# ELED04.net
KiCad netlist of a schematic drawn in EAGLE
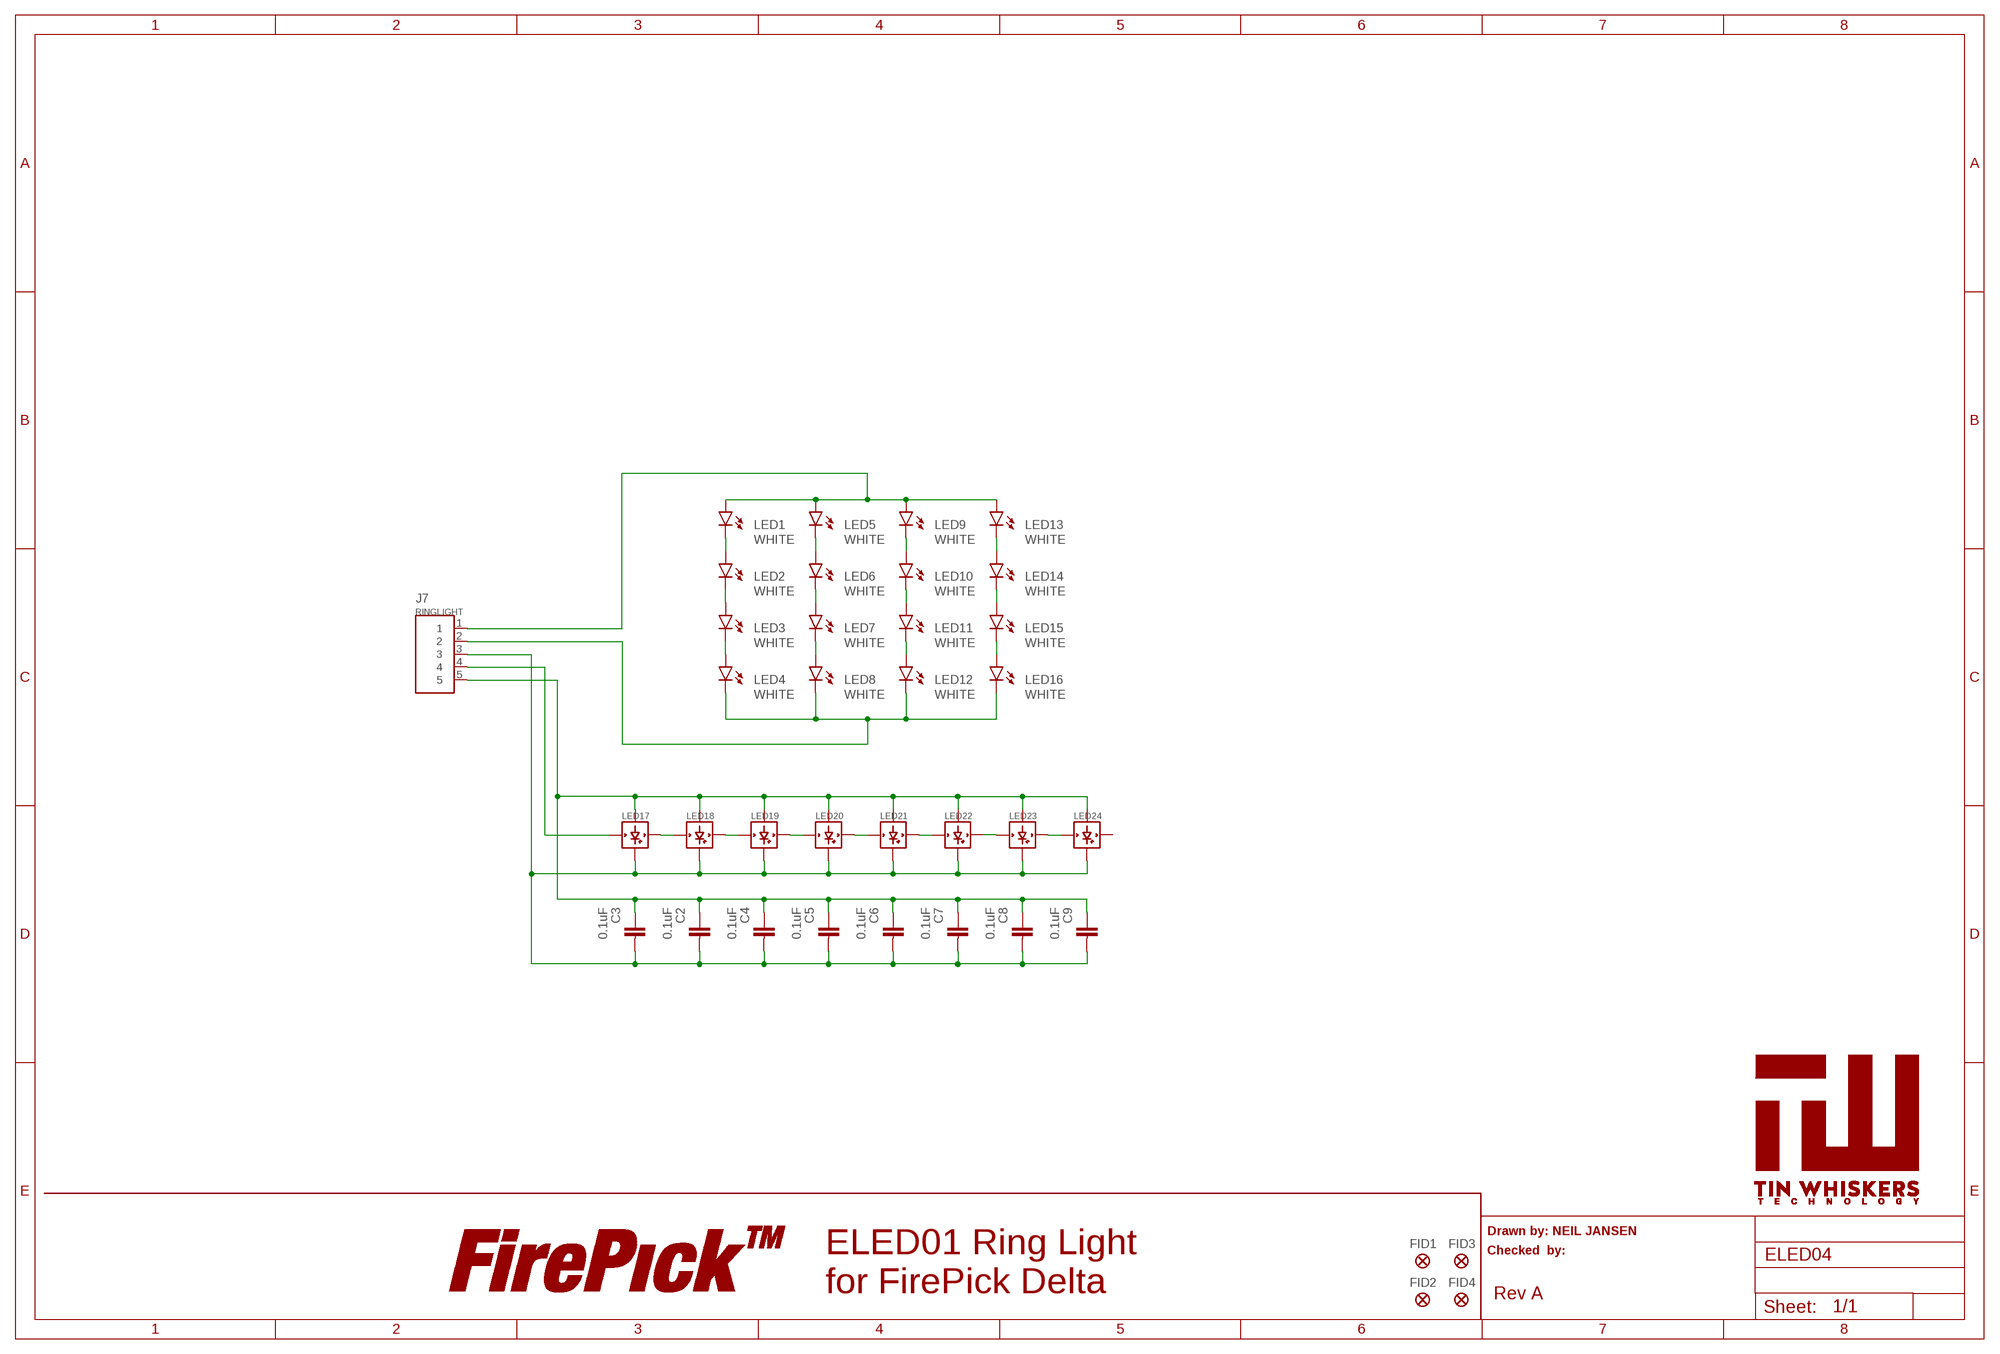
[diagram p0: schematic, sheet 1]

(export (version "E")
  (design (tool "Eeschema 10.0.6"))
  (components
    (comp (ref "C2")
      (value "0.1uF")
      (footprint "eagle-import:C0603")
      (fields (field (name "PARTNO") "GMK107BJ104KAHT"))
      (libsource (lib "eagle-import") (part "CPL-CAP-X5R-0603-0.1UF-35V"))
    )
    (comp (ref "C3")
      (value "0.1uF")
      (footprint "eagle-import:C0603")
      (fields (field (name "PARTNO") "GMK107BJ104KAHT"))
      (libsource (lib "eagle-import") (part "CPL-CAP-X5R-0603-0.1UF-35V"))
    )
    (comp (ref "C4")
      (value "0.1uF")
      (footprint "eagle-import:C0603")
      (fields (field (name "PARTNO") "GMK107BJ104KAHT"))
      (libsource (lib "eagle-import") (part "CPL-CAP-X5R-0603-0.1UF-35V"))
    )
    (comp (ref "C5")
      (value "0.1uF")
      (footprint "eagle-import:C0603")
      (fields (field (name "PARTNO") "GMK107BJ104KAHT"))
      (libsource (lib "eagle-import") (part "CPL-CAP-X5R-0603-0.1UF-35V"))
    )
    (comp (ref "C6")
      (value "0.1uF")
      (footprint "eagle-import:C0603")
      (fields (field (name "PARTNO") "GMK107BJ104KAHT"))
      (libsource (lib "eagle-import") (part "CPL-CAP-X5R-0603-0.1UF-35V"))
    )
    (comp (ref "C7")
      (value "0.1uF")
      (footprint "eagle-import:C0603")
      (fields (field (name "PARTNO") "GMK107BJ104KAHT"))
      (libsource (lib "eagle-import") (part "CPL-CAP-X5R-0603-0.1UF-35V"))
    )
    (comp (ref "C8")
      (value "0.1uF")
      (footprint "eagle-import:C0603")
      (fields (field (name "PARTNO") "GMK107BJ104KAHT"))
      (libsource (lib "eagle-import") (part "CPL-CAP-X5R-0603-0.1UF-35V"))
    )
    (comp (ref "C9")
      (value "0.1uF")
      (footprint "eagle-import:C0603")
      (fields (field (name "PARTNO") "GMK107BJ104KAHT"))
      (libsource (lib "eagle-import") (part "CPL-CAP-X5R-0603-0.1UF-35V"))
    )
    (comp (ref "FID1")
      (value "FIDUCIAL")
      (footprint "eagle-import:FIDUCIAL")
      (libsource (lib "eagle-import") (part "FIDUCIAL"))
    )
    (comp (ref "FID2")
      (value "FIDUCIAL")
      (footprint "eagle-import:FIDUCIAL")
      (libsource (lib "eagle-import") (part "FIDUCIAL"))
    )
    (comp (ref "FID3")
      (value "FIDUCIAL")
      (footprint "eagle-import:FIDUCIAL")
      (libsource (lib "eagle-import") (part "FIDUCIAL"))
    )
    (comp (ref "FID4")
      (value "FIDUCIAL")
      (footprint "eagle-import:FIDUCIAL")
      (libsource (lib "eagle-import") (part "FIDUCIAL"))
    )
    (comp (ref "J7")
      (value "RINGLIGHT")
      (footprint "eagle-import:CON-JST-PH-2.0MM-5P-SMT-VRT")
      (fields (field (name "PARTNO") "B5B-PH-SM4-TB(LF)(SN)"))
      (libsource (lib "eagle-import") (part "CPL-CON-JST-2.0MM-5P-SMT-VRT"))
    )
    (comp (ref "LED1")
      (value "WHITE")
      (footprint "eagle-import:DIODE-1210")
      (fields (field (name "PARTNO") "QBLP650-IW"))
      (libsource (lib "eagle-import") (part "LED1210"))
    )
    (comp (ref "LED2")
      (value "WHITE")
      (footprint "eagle-import:DIODE-1210")
      (fields (field (name "PARTNO") "QBLP650-IW"))
      (libsource (lib "eagle-import") (part "LED1210"))
    )
    (comp (ref "LED3")
      (value "WHITE")
      (footprint "eagle-import:DIODE-1210")
      (fields (field (name "PARTNO") "QBLP650-IW"))
      (libsource (lib "eagle-import") (part "LED1210"))
    )
    (comp (ref "LED4")
      (value "WHITE")
      (footprint "eagle-import:DIODE-1210")
      (fields (field (name "PARTNO") "QBLP650-IW"))
      (libsource (lib "eagle-import") (part "LED1210"))
    )
    (comp (ref "LED5")
      (value "WHITE")
      (footprint "eagle-import:DIODE-1210")
      (fields (field (name "PARTNO") "QBLP650-IW"))
      (libsource (lib "eagle-import") (part "LED1210"))
    )
    (comp (ref "LED6")
      (value "WHITE")
      (footprint "eagle-import:DIODE-1210")
      (fields (field (name "PARTNO") "QBLP650-IW"))
      (libsource (lib "eagle-import") (part "LED1210"))
    )
    (comp (ref "LED7")
      (value "WHITE")
      (footprint "eagle-import:DIODE-1210")
      (fields (field (name "PARTNO") "QBLP650-IW"))
      (libsource (lib "eagle-import") (part "LED1210"))
    )
    (comp (ref "LED8")
      (value "WHITE")
      (footprint "eagle-import:DIODE-1210")
      (fields (field (name "PARTNO") "QBLP650-IW"))
      (libsource (lib "eagle-import") (part "LED1210"))
    )
    (comp (ref "LED9")
      (value "WHITE")
      (footprint "eagle-import:DIODE-1210")
      (fields (field (name "PARTNO") "QBLP650-IW"))
      (libsource (lib "eagle-import") (part "LED1210"))
    )
    (comp (ref "LED10")
      (value "WHITE")
      (footprint "eagle-import:DIODE-1210")
      (fields (field (name "PARTNO") "QBLP650-IW"))
      (libsource (lib "eagle-import") (part "LED1210"))
    )
    (comp (ref "LED11")
      (value "WHITE")
      (footprint "eagle-import:DIODE-1210")
      (fields (field (name "PARTNO") "QBLP650-IW"))
      (libsource (lib "eagle-import") (part "LED1210"))
    )
    (comp (ref "LED12")
      (value "WHITE")
      (footprint "eagle-import:DIODE-1210")
      (fields (field (name "PARTNO") "QBLP650-IW"))
      (libsource (lib "eagle-import") (part "LED1210"))
    )
    (comp (ref "LED13")
      (value "WHITE")
      (footprint "eagle-import:DIODE-1210")
      (fields (field (name "PARTNO") "QBLP650-IW"))
      (libsource (lib "eagle-import") (part "LED1210"))
    )
    (comp (ref "LED14")
      (value "WHITE")
      (footprint "eagle-import:DIODE-1210")
      (fields (field (name "PARTNO") "QBLP650-IW"))
      (libsource (lib "eagle-import") (part "LED1210"))
    )
    (comp (ref "LED15")
      (value "WHITE")
      (footprint "eagle-import:DIODE-1210")
      (fields (field (name "PARTNO") "QBLP650-IW"))
      (libsource (lib "eagle-import") (part "LED1210"))
    )
    (comp (ref "LED16")
      (value "WHITE")
      (footprint "eagle-import:DIODE-1210")
      (fields (field (name "PARTNO") "QBLP650-IW"))
      (libsource (lib "eagle-import") (part "LED1210"))
    )
    (comp (ref "LED17")
      (value "WS2812B")
      (footprint "eagle-import:WS2812B")
      (fields (field (name "PARTNO") "1655"))
      (libsource (lib "eagle-import") (part "WS2812B"))
    )
    (comp (ref "LED18")
      (value "WS2812B")
      (footprint "eagle-import:WS2812B")
      (fields (field (name "PARTNO") "1655"))
      (libsource (lib "eagle-import") (part "WS2812B"))
    )
    (comp (ref "LED19")
      (value "WS2812B")
      (footprint "eagle-import:WS2812B")
      (fields (field (name "PARTNO") "1655"))
      (libsource (lib "eagle-import") (part "WS2812B"))
    )
    (comp (ref "LED20")
      (value "WS2812B")
      (footprint "eagle-import:WS2812B")
      (fields (field (name "PARTNO") "1655"))
      (libsource (lib "eagle-import") (part "WS2812B"))
    )
    (comp (ref "LED21")
      (value "WS2812B")
      (footprint "eagle-import:WS2812B")
      (fields (field (name "PARTNO") "1655"))
      (libsource (lib "eagle-import") (part "WS2812B"))
    )
    (comp (ref "LED22")
      (value "WS2812B")
      (footprint "eagle-import:WS2812B")
      (fields (field (name "PARTNO") "1655"))
      (libsource (lib "eagle-import") (part "WS2812B"))
    )
    (comp (ref "LED23")
      (value "WS2812B")
      (footprint "eagle-import:WS2812B")
      (fields (field (name "PARTNO") "1655"))
      (libsource (lib "eagle-import") (part "WS2812B"))
    )
    (comp (ref "LED24")
      (value "WS2812B")
      (footprint "eagle-import:WS2812B")
      (fields (field (name "PARTNO") "1655"))
      (libsource (lib "eagle-import") (part "WS2812B"))
    )
    (comp (ref "LOGO4")
      (value "LOGO-FIREPICKMEDIUM")
      (footprint "eagle-import:LOGO-FIREPICK-MEDIUM")
      (libsource (lib "eagle-import") (part "LOGO-FIREPICKMEDIUM"))
    )
    (comp (ref "U$3")
      (value "TIN-WHISKERSSMALL")
      (footprint "eagle-import:TIN-WHISKERS-SMALL")
      (libsource (lib "eagle-import") (part "TIN-WHISKERSSMALL"))
    )
  )
  (nets
    (net (code "1") (name "Net-(J7-Pad1)") (class "Default")
      (node (ref "J7") (pin "1") (pinfunction "1_1") (pintype "bidirectional"))
      (node (ref "LED1") (pin "A") (pinfunction "A_A") (pintype "passive"))
      (node (ref "LED13") (pin "A") (pinfunction "A_A") (pintype "passive"))
      (node (ref "LED5") (pin "A") (pinfunction "A_A") (pintype "passive"))
      (node (ref "LED9") (pin "A") (pinfunction "A_A") (pintype "passive"))
    )
    (net (code "2") (name "Net-(LED1-C)") (class "Default")
      (node (ref "LED1") (pin "K") (pinfunction "C_K") (pintype "passive"))
      (node (ref "LED2") (pin "A") (pinfunction "A_A") (pintype "passive"))
    )
    (net (code "3") (name "Net-(LED2-C)") (class "Default")
      (node (ref "LED2") (pin "K") (pinfunction "C_K") (pintype "passive"))
      (node (ref "LED3") (pin "A") (pinfunction "A_A") (pintype "passive"))
    )
    (net (code "4") (name "Net-(LED3-C)") (class "Default")
      (node (ref "LED3") (pin "K") (pinfunction "C_K") (pintype "passive"))
      (node (ref "LED4") (pin "A") (pinfunction "A_A") (pintype "passive"))
    )
    (net (code "5") (name "Net-(LED5-C)") (class "Default")
      (node (ref "LED5") (pin "K") (pinfunction "C_K") (pintype "passive"))
      (node (ref "LED6") (pin "A") (pinfunction "A_A") (pintype "passive"))
    )
    (net (code "6") (name "Net-(LED6-C)") (class "Default")
      (node (ref "LED6") (pin "K") (pinfunction "C_K") (pintype "passive"))
      (node (ref "LED7") (pin "A") (pinfunction "A_A") (pintype "passive"))
    )
    (net (code "7") (name "Net-(LED7-C)") (class "Default")
      (node (ref "LED7") (pin "K") (pinfunction "C_K") (pintype "passive"))
      (node (ref "LED8") (pin "A") (pinfunction "A_A") (pintype "passive"))
    )
    (net (code "8") (name "Net-(LED9-C)") (class "Default")
      (node (ref "LED10") (pin "A") (pinfunction "A_A") (pintype "passive"))
      (node (ref "LED9") (pin "K") (pinfunction "C_K") (pintype "passive"))
    )
    (net (code "9") (name "Net-(LED10-C)") (class "Default")
      (node (ref "LED10") (pin "K") (pinfunction "C_K") (pintype "passive"))
      (node (ref "LED11") (pin "A") (pinfunction "A_A") (pintype "passive"))
    )
    (net (code "10") (name "Net-(LED11-C)") (class "Default")
      (node (ref "LED11") (pin "K") (pinfunction "C_K") (pintype "passive"))
      (node (ref "LED12") (pin "A") (pinfunction "A_A") (pintype "passive"))
    )
    (net (code "11") (name "Net-(LED12-C)") (class "Default")
      (node (ref "J7") (pin "2") (pinfunction "2_2") (pintype "bidirectional"))
      (node (ref "LED12") (pin "K") (pinfunction "C_K") (pintype "passive"))
      (node (ref "LED16") (pin "K") (pinfunction "C_K") (pintype "passive"))
      (node (ref "LED4") (pin "K") (pinfunction "C_K") (pintype "passive"))
      (node (ref "LED8") (pin "K") (pinfunction "C_K") (pintype "passive"))
    )
    (net (code "12") (name "Net-(LED13-C)") (class "Default")
      (node (ref "LED13") (pin "K") (pinfunction "C_K") (pintype "passive"))
      (node (ref "LED14") (pin "A") (pinfunction "A_A") (pintype "passive"))
    )
    (net (code "13") (name "Net-(LED14-C)") (class "Default")
      (node (ref "LED14") (pin "K") (pinfunction "C_K") (pintype "passive"))
      (node (ref "LED15") (pin "A") (pinfunction "A_A") (pintype "passive"))
    )
    (net (code "14") (name "Net-(LED15-C)") (class "Default")
      (node (ref "LED15") (pin "K") (pinfunction "C_K") (pintype "passive"))
      (node (ref "LED16") (pin "A") (pinfunction "A_A") (pintype "passive"))
    )
    (net (code "15") (name "Net-(LED17-DIN)") (class "Default")
      (node (ref "J7") (pin "4") (pinfunction "4_4") (pintype "bidirectional"))
      (node (ref "LED17") (pin "4-DIN") (pinfunction "DIN_4-DIN") (pintype "input"))
    )
    (net (code "16") (name "Net-(LED17-DOUT)") (class "Default")
      (node (ref "LED17") (pin "2-DOUT") (pinfunction "DOUT_2-DOUT") (pintype "output"))
      (node (ref "LED18") (pin "4-DIN") (pinfunction "DIN_4-DIN") (pintype "input"))
    )
    (net (code "17") (name "Net-(LED17-GND)") (class "Default")
      (node (ref "C2") (pin "2") (pinfunction "2_2") (pintype "passive"))
      (node (ref "C3") (pin "2") (pinfunction "2_2") (pintype "passive"))
      (node (ref "C4") (pin "2") (pinfunction "2_2") (pintype "passive"))
      (node (ref "C5") (pin "2") (pinfunction "2_2") (pintype "passive"))
      (node (ref "C6") (pin "2") (pinfunction "2_2") (pintype "passive"))
      (node (ref "C7") (pin "2") (pinfunction "2_2") (pintype "passive"))
      (node (ref "C8") (pin "2") (pinfunction "2_2") (pintype "passive"))
      (node (ref "C9") (pin "2") (pinfunction "2_2") (pintype "passive"))
      (node (ref "J7") (pin "3") (pinfunction "3_3") (pintype "bidirectional"))
      (node (ref "LED17") (pin "3-GND") (pinfunction "GND_3-GND") (pintype "bidirectional"))
      (node (ref "LED18") (pin "3-GND") (pinfunction "GND_3-GND") (pintype "bidirectional"))
      (node (ref "LED19") (pin "3-GND") (pinfunction "GND_3-GND") (pintype "bidirectional"))
      (node (ref "LED20") (pin "3-GND") (pinfunction "GND_3-GND") (pintype "bidirectional"))
      (node (ref "LED21") (pin "3-GND") (pinfunction "GND_3-GND") (pintype "bidirectional"))
      (node (ref "LED22") (pin "3-GND") (pinfunction "GND_3-GND") (pintype "bidirectional"))
      (node (ref "LED23") (pin "3-GND") (pinfunction "GND_3-GND") (pintype "bidirectional"))
      (node (ref "LED24") (pin "3-GND") (pinfunction "GND_3-GND") (pintype "bidirectional"))
    )
    (net (code "18") (name "Net-(LED17-VDD)") (class "Default")
      (node (ref "C2") (pin "1") (pinfunction "1_1") (pintype "passive"))
      (node (ref "C3") (pin "1") (pinfunction "1_1") (pintype "passive"))
      (node (ref "C4") (pin "1") (pinfunction "1_1") (pintype "passive"))
      (node (ref "C5") (pin "1") (pinfunction "1_1") (pintype "passive"))
      (node (ref "C6") (pin "1") (pinfunction "1_1") (pintype "passive"))
      (node (ref "C7") (pin "1") (pinfunction "1_1") (pintype "passive"))
      (node (ref "C8") (pin "1") (pinfunction "1_1") (pintype "passive"))
      (node (ref "C9") (pin "1") (pinfunction "1_1") (pintype "passive"))
      (node (ref "J7") (pin "5") (pinfunction "5_5") (pintype "bidirectional"))
      (node (ref "LED17") (pin "1-VDD") (pinfunction "VDD_1-VDD") (pintype "bidirectional"))
      (node (ref "LED18") (pin "1-VDD") (pinfunction "VDD_1-VDD") (pintype "bidirectional"))
      (node (ref "LED19") (pin "1-VDD") (pinfunction "VDD_1-VDD") (pintype "bidirectional"))
      (node (ref "LED20") (pin "1-VDD") (pinfunction "VDD_1-VDD") (pintype "bidirectional"))
      (node (ref "LED21") (pin "1-VDD") (pinfunction "VDD_1-VDD") (pintype "bidirectional"))
      (node (ref "LED22") (pin "1-VDD") (pinfunction "VDD_1-VDD") (pintype "bidirectional"))
      (node (ref "LED23") (pin "1-VDD") (pinfunction "VDD_1-VDD") (pintype "bidirectional"))
      (node (ref "LED24") (pin "1-VDD") (pinfunction "VDD_1-VDD") (pintype "bidirectional"))
    )
    (net (code "19") (name "Net-(LED18-DOUT)") (class "Default")
      (node (ref "LED18") (pin "2-DOUT") (pinfunction "DOUT_2-DOUT") (pintype "output"))
      (node (ref "LED19") (pin "4-DIN") (pinfunction "DIN_4-DIN") (pintype "input"))
    )
    (net (code "20") (name "Net-(LED19-DOUT)") (class "Default")
      (node (ref "LED19") (pin "2-DOUT") (pinfunction "DOUT_2-DOUT") (pintype "output"))
      (node (ref "LED20") (pin "4-DIN") (pinfunction "DIN_4-DIN") (pintype "input"))
    )
    (net (code "21") (name "Net-(LED20-DOUT)") (class "Default")
      (node (ref "LED20") (pin "2-DOUT") (pinfunction "DOUT_2-DOUT") (pintype "output"))
      (node (ref "LED21") (pin "4-DIN") (pinfunction "DIN_4-DIN") (pintype "input"))
    )
    (net (code "22") (name "Net-(LED21-DOUT)") (class "Default")
      (node (ref "LED21") (pin "2-DOUT") (pinfunction "DOUT_2-DOUT") (pintype "output"))
      (node (ref "LED22") (pin "4-DIN") (pinfunction "DIN_4-DIN") (pintype "input"))
    )
    (net (code "23") (name "Net-(LED22-DOUT)") (class "Default")
      (node (ref "LED22") (pin "2-DOUT") (pinfunction "DOUT_2-DOUT") (pintype "output"))
      (node (ref "LED23") (pin "4-DIN") (pinfunction "DIN_4-DIN") (pintype "input"))
    )
    (net (code "24") (name "Net-(LED23-DOUT)") (class "Default")
      (node (ref "LED23") (pin "2-DOUT") (pinfunction "DOUT_2-DOUT") (pintype "output"))
      (node (ref "LED24") (pin "4-DIN") (pinfunction "DIN_4-DIN") (pintype "input"))
    )
    (net (code "25") (name "unconnected-(LED24-DOUT-Pad2-DOUT)") (class "Default")
      (node (ref "LED24") (pin "2-DOUT") (pinfunction "DOUT_2-DOUT") (pintype "output"))
    )
  )
)
